# 0805_array.net
KiCad netlist of a schematic drawn in Altium Designer
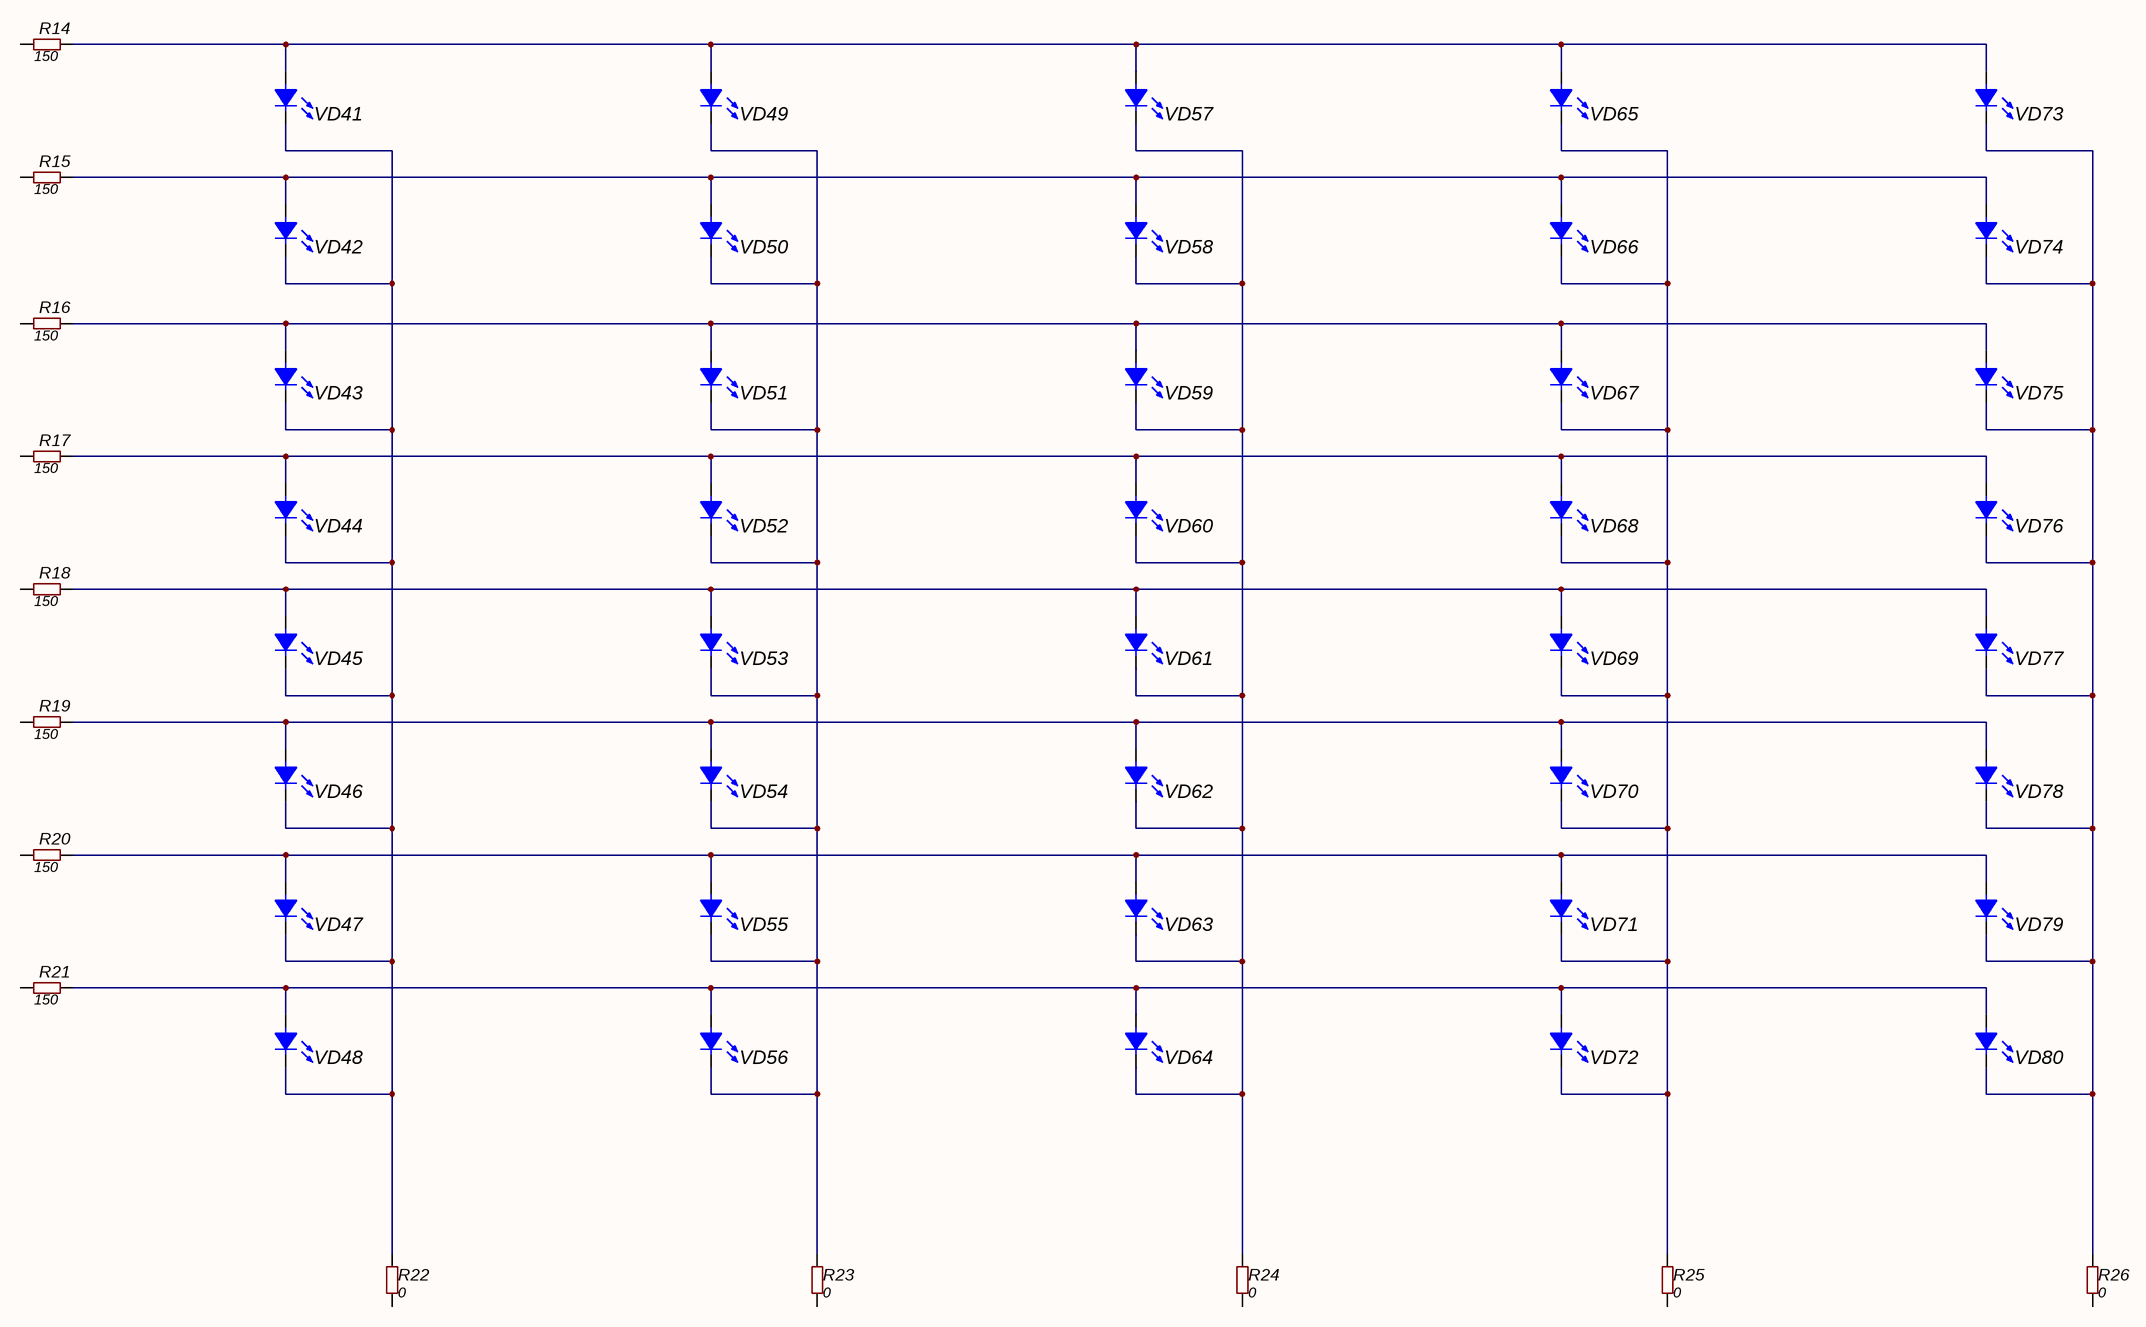
[diagram p0: 0805_array.SchDoc]

(export (version "E")
  (design (tool "Eeschema 10.0.6"))
  (components
    (comp (ref "R14")
      (value "150")
      (footprint "RES: 0603")
      (fields
        (field (name "MANUFACTURER") "Yageo")
        (field (name "PARTNUMBER") "RC0603JR-07100RL")
        (field (name "VALUEMANUFACTURERPARTNUMBER") "Resistor film, 150, , 0603, 0.1W, -55...+125°C")
      )
      (libsource (lib "") (part "Resistor_0603_1"))
    )
    (comp (ref "R15")
      (value "150")
      (footprint "RES: 0603")
      (fields
        (field (name "MANUFACTURER") "Yageo")
        (field (name "PARTNUMBER") "RC0603JR-07100RL")
        (field (name "VALUEMANUFACTURERPARTNUMBER") "Resistor film, 150, , 0603, 0.1W, -55...+125°C")
      )
      (libsource (lib "") (part "Resistor_0603_1"))
    )
    (comp (ref "R16")
      (value "150")
      (footprint "RES: 0603")
      (fields
        (field (name "MANUFACTURER") "Yageo")
        (field (name "PARTNUMBER") "RC0603JR-07100RL")
        (field (name "VALUEMANUFACTURERPARTNUMBER") "Resistor film, 150, , 0603, 0.1W, -55...+125°C")
      )
      (libsource (lib "") (part "Resistor_0603_1"))
    )
    (comp (ref "R17")
      (value "150")
      (footprint "RES: 0603")
      (fields
        (field (name "MANUFACTURER") "Yageo")
        (field (name "PARTNUMBER") "RC0603JR-07100RL")
        (field (name "VALUEMANUFACTURERPARTNUMBER") "Resistor film, 150, , 0603, 0.1W, -55...+125°C")
      )
      (libsource (lib "") (part "Resistor_0603_1"))
    )
    (comp (ref "R18")
      (value "150")
      (footprint "RES: 0603")
      (fields
        (field (name "MANUFACTURER") "Yageo")
        (field (name "PARTNUMBER") "RC0603JR-07100RL")
        (field (name "VALUEMANUFACTURERPARTNUMBER") "Resistor film, 150, , 0603, 0.1W, -55...+125°C")
      )
      (libsource (lib "") (part "Resistor_0603_1"))
    )
    (comp (ref "R19")
      (value "150")
      (footprint "RES: 0603")
      (fields
        (field (name "MANUFACTURER") "Yageo")
        (field (name "PARTNUMBER") "RC0603JR-07100RL")
        (field (name "VALUEMANUFACTURERPARTNUMBER") "Resistor film, 150, , 0603, 0.1W, -55...+125°C")
      )
      (libsource (lib "") (part "Resistor_0603_1"))
    )
    (comp (ref "R20")
      (value "150")
      (footprint "RES: 0603")
      (fields
        (field (name "MANUFACTURER") "Yageo")
        (field (name "PARTNUMBER") "RC0603JR-07100RL")
        (field (name "VALUEMANUFACTURERPARTNUMBER") "Resistor film, 150, , 0603, 0.1W, -55...+125°C")
      )
      (libsource (lib "") (part "Resistor_0603_1"))
    )
    (comp (ref "R21")
      (value "150")
      (footprint "RES: 0603")
      (fields
        (field (name "MANUFACTURER") "Yageo")
        (field (name "PARTNUMBER") "RC0603JR-07100RL")
        (field (name "VALUEMANUFACTURERPARTNUMBER") "Resistor film, 150, , 0603, 0.1W, -55...+125°C")
      )
      (libsource (lib "") (part "Resistor_0603_1"))
    )
    (comp (ref "R22")
      (value "0")
      (footprint "RES: 0603")
      (fields
        (field (name "MANUFACTURER") "Yageo")
        (field (name "PARTNUMBER") "RC0603JR-07100RL")
        (field (name "VALUEMANUFACTURERPARTNUMBER") "Resistor film, 0, , 0603, 0.1W, -55...+125°C")
      )
      (libsource (lib "resistor") (part "Resistor_0603"))
    )
    (comp (ref "R23")
      (value "0")
      (footprint "RES: 0603")
      (fields
        (field (name "MANUFACTURER") "Yageo")
        (field (name "PARTNUMBER") "RC0603JR-07100RL")
        (field (name "VALUEMANUFACTURERPARTNUMBER") "Resistor film, 0, , 0603, 0.1W, -55...+125°C")
      )
      (libsource (lib "resistor") (part "Resistor_0603"))
    )
    (comp (ref "R24")
      (value "0")
      (footprint "RES: 0603")
      (fields
        (field (name "MANUFACTURER") "Yageo")
        (field (name "PARTNUMBER") "RC0603JR-07100RL")
        (field (name "VALUEMANUFACTURERPARTNUMBER") "Resistor film, 0, , 0603, 0.1W, -55...+125°C")
      )
      (libsource (lib "resistor") (part "Resistor_0603"))
    )
    (comp (ref "R25")
      (value "0")
      (footprint "RES: 0603")
      (fields
        (field (name "MANUFACTURER") "Yageo")
        (field (name "PARTNUMBER") "RC0603JR-07100RL")
        (field (name "VALUEMANUFACTURERPARTNUMBER") "Resistor film, 0, , 0603, 0.1W, -55...+125°C")
      )
      (libsource (lib "resistor") (part "Resistor_0603"))
    )
    (comp (ref "R26")
      (value "0")
      (footprint "RES: 0603")
      (fields
        (field (name "MANUFACTURER") "Yageo")
        (field (name "PARTNUMBER") "RC0603JR-07100RL")
        (field (name "VALUEMANUFACTURERPARTNUMBER") "Resistor film, 0, , 0603, 0.1W, -55...+125°C")
      )
      (libsource (lib "resistor") (part "Resistor_0603"))
    )
    (comp (ref "VD41")
      (value "~")
      (footprint "LED: 0805Y")
      (fields (field (name "VALUEMANUFACTURERPARTNUMBER") "LED, Green, *, *, *, -55...+150°C"))
      (libsource (lib "diode") (part "LED_single"))
    )
    (comp (ref "VD42")
      (value "~")
      (footprint "LED: 0805Y")
      (fields (field (name "VALUEMANUFACTURERPARTNUMBER") "LED, Green, *, *, *, -55...+150°C"))
      (libsource (lib "diode") (part "LED_single"))
    )
    (comp (ref "VD43")
      (value "~")
      (footprint "LED: 0805Y")
      (fields (field (name "VALUEMANUFACTURERPARTNUMBER") "LED, Green, *, *, *, -55...+150°C"))
      (libsource (lib "diode") (part "LED_single"))
    )
    (comp (ref "VD44")
      (value "~")
      (footprint "LED: 0805Y")
      (fields (field (name "VALUEMANUFACTURERPARTNUMBER") "LED, Green, *, *, *, -55...+150°C"))
      (libsource (lib "diode") (part "LED_single"))
    )
    (comp (ref "VD45")
      (value "~")
      (footprint "LED: 0805Y")
      (fields (field (name "VALUEMANUFACTURERPARTNUMBER") "LED, Green, *, *, *, -55...+150°C"))
      (libsource (lib "diode") (part "LED_single"))
    )
    (comp (ref "VD46")
      (value "~")
      (footprint "LED: 0805Y")
      (fields (field (name "VALUEMANUFACTURERPARTNUMBER") "LED, Green, *, *, *, -55...+150°C"))
      (libsource (lib "diode") (part "LED_single"))
    )
    (comp (ref "VD47")
      (value "~")
      (footprint "LED: 0805Y")
      (fields (field (name "VALUEMANUFACTURERPARTNUMBER") "LED, Green, *, *, *, -55...+150°C"))
      (libsource (lib "diode") (part "LED_single"))
    )
    (comp (ref "VD48")
      (value "~")
      (footprint "LED: 0805Y")
      (fields (field (name "VALUEMANUFACTURERPARTNUMBER") "LED, Green, *, *, *, -55...+150°C"))
      (libsource (lib "diode") (part "LED_single"))
    )
    (comp (ref "VD49")
      (value "~")
      (footprint "LED: 0805Y")
      (fields (field (name "VALUEMANUFACTURERPARTNUMBER") "LED, Green, *, *, *, -55...+150°C"))
      (libsource (lib "diode") (part "LED_single"))
    )
    (comp (ref "VD50")
      (value "~")
      (footprint "LED: 0805Y")
      (fields (field (name "VALUEMANUFACTURERPARTNUMBER") "LED, Green, *, *, *, -55...+150°C"))
      (libsource (lib "diode") (part "LED_single"))
    )
    (comp (ref "VD51")
      (value "~")
      (footprint "LED: 0805Y")
      (fields (field (name "VALUEMANUFACTURERPARTNUMBER") "LED, Green, *, *, *, -55...+150°C"))
      (libsource (lib "diode") (part "LED_single"))
    )
    (comp (ref "VD52")
      (value "~")
      (footprint "LED: 0805Y")
      (fields (field (name "VALUEMANUFACTURERPARTNUMBER") "LED, Green, *, *, *, -55...+150°C"))
      (libsource (lib "diode") (part "LED_single"))
    )
    (comp (ref "VD53")
      (value "~")
      (footprint "LED: 0805Y")
      (fields (field (name "VALUEMANUFACTURERPARTNUMBER") "LED, Green, *, *, *, -55...+150°C"))
      (libsource (lib "diode") (part "LED_single"))
    )
    (comp (ref "VD54")
      (value "~")
      (footprint "LED: 0805Y")
      (fields (field (name "VALUEMANUFACTURERPARTNUMBER") "LED, Green, *, *, *, -55...+150°C"))
      (libsource (lib "diode") (part "LED_single"))
    )
    (comp (ref "VD55")
      (value "~")
      (footprint "LED: 0805Y")
      (fields (field (name "VALUEMANUFACTURERPARTNUMBER") "LED, Green, *, *, *, -55...+150°C"))
      (libsource (lib "diode") (part "LED_single"))
    )
    (comp (ref "VD56")
      (value "~")
      (footprint "LED: 0805Y")
      (fields (field (name "VALUEMANUFACTURERPARTNUMBER") "LED, Green, *, *, *, -55...+150°C"))
      (libsource (lib "diode") (part "LED_single"))
    )
    (comp (ref "VD57")
      (value "~")
      (footprint "LED: 0805Y")
      (fields (field (name "VALUEMANUFACTURERPARTNUMBER") "LED, Green, *, *, *, -55...+150°C"))
      (libsource (lib "diode") (part "LED_single"))
    )
    (comp (ref "VD58")
      (value "~")
      (footprint "LED: 0805Y")
      (fields (field (name "VALUEMANUFACTURERPARTNUMBER") "LED, Green, *, *, *, -55...+150°C"))
      (libsource (lib "diode") (part "LED_single"))
    )
    (comp (ref "VD59")
      (value "~")
      (footprint "LED: 0805Y")
      (fields (field (name "VALUEMANUFACTURERPARTNUMBER") "LED, Green, *, *, *, -55...+150°C"))
      (libsource (lib "diode") (part "LED_single"))
    )
    (comp (ref "VD60")
      (value "~")
      (footprint "LED: 0805Y")
      (fields (field (name "VALUEMANUFACTURERPARTNUMBER") "LED, Green, *, *, *, -55...+150°C"))
      (libsource (lib "diode") (part "LED_single"))
    )
    (comp (ref "VD61")
      (value "~")
      (footprint "LED: 0805Y")
      (fields (field (name "VALUEMANUFACTURERPARTNUMBER") "LED, Green, *, *, *, -55...+150°C"))
      (libsource (lib "diode") (part "LED_single"))
    )
    (comp (ref "VD62")
      (value "~")
      (footprint "LED: 0805Y")
      (fields (field (name "VALUEMANUFACTURERPARTNUMBER") "LED, Green, *, *, *, -55...+150°C"))
      (libsource (lib "diode") (part "LED_single"))
    )
    (comp (ref "VD63")
      (value "~")
      (footprint "LED: 0805Y")
      (fields (field (name "VALUEMANUFACTURERPARTNUMBER") "LED, Green, *, *, *, -55...+150°C"))
      (libsource (lib "diode") (part "LED_single"))
    )
    (comp (ref "VD64")
      (value "~")
      (footprint "LED: 0805Y")
      (fields (field (name "VALUEMANUFACTURERPARTNUMBER") "LED, Green, *, *, *, -55...+150°C"))
      (libsource (lib "diode") (part "LED_single"))
    )
    (comp (ref "VD65")
      (value "~")
      (footprint "LED: 0805Y")
      (fields (field (name "VALUEMANUFACTURERPARTNUMBER") "LED, Green, *, *, *, -55...+150°C"))
      (libsource (lib "diode") (part "LED_single"))
    )
    (comp (ref "VD66")
      (value "~")
      (footprint "LED: 0805Y")
      (fields (field (name "VALUEMANUFACTURERPARTNUMBER") "LED, Green, *, *, *, -55...+150°C"))
      (libsource (lib "diode") (part "LED_single"))
    )
    (comp (ref "VD67")
      (value "~")
      (footprint "LED: 0805Y")
      (fields (field (name "VALUEMANUFACTURERPARTNUMBER") "LED, Green, *, *, *, -55...+150°C"))
      (libsource (lib "diode") (part "LED_single"))
    )
    (comp (ref "VD68")
      (value "~")
      (footprint "LED: 0805Y")
      (fields (field (name "VALUEMANUFACTURERPARTNUMBER") "LED, Green, *, *, *, -55...+150°C"))
      (libsource (lib "diode") (part "LED_single"))
    )
    (comp (ref "VD69")
      (value "~")
      (footprint "LED: 0805Y")
      (fields (field (name "VALUEMANUFACTURERPARTNUMBER") "LED, Green, *, *, *, -55...+150°C"))
      (libsource (lib "diode") (part "LED_single"))
    )
    (comp (ref "VD70")
      (value "~")
      (footprint "LED: 0805Y")
      (fields (field (name "VALUEMANUFACTURERPARTNUMBER") "LED, Green, *, *, *, -55...+150°C"))
      (libsource (lib "diode") (part "LED_single"))
    )
    (comp (ref "VD71")
      (value "~")
      (footprint "LED: 0805Y")
      (fields (field (name "VALUEMANUFACTURERPARTNUMBER") "LED, Green, *, *, *, -55...+150°C"))
      (libsource (lib "diode") (part "LED_single"))
    )
    (comp (ref "VD72")
      (value "~")
      (footprint "LED: 0805Y")
      (fields (field (name "VALUEMANUFACTURERPARTNUMBER") "LED, Green, *, *, *, -55...+150°C"))
      (libsource (lib "diode") (part "LED_single"))
    )
    (comp (ref "VD73")
      (value "~")
      (footprint "LED: 0805Y")
      (fields (field (name "VALUEMANUFACTURERPARTNUMBER") "LED, Green, *, *, *, -55...+150°C"))
      (libsource (lib "diode") (part "LED_single"))
    )
    (comp (ref "VD74")
      (value "~")
      (footprint "LED: 0805Y")
      (fields (field (name "VALUEMANUFACTURERPARTNUMBER") "LED, Green, *, *, *, -55...+150°C"))
      (libsource (lib "diode") (part "LED_single"))
    )
    (comp (ref "VD75")
      (value "~")
      (footprint "LED: 0805Y")
      (fields (field (name "VALUEMANUFACTURERPARTNUMBER") "LED, Green, *, *, *, -55...+150°C"))
      (libsource (lib "diode") (part "LED_single"))
    )
    (comp (ref "VD76")
      (value "~")
      (footprint "LED: 0805Y")
      (fields (field (name "VALUEMANUFACTURERPARTNUMBER") "LED, Green, *, *, *, -55...+150°C"))
      (libsource (lib "diode") (part "LED_single"))
    )
    (comp (ref "VD77")
      (value "~")
      (footprint "LED: 0805Y")
      (fields (field (name "VALUEMANUFACTURERPARTNUMBER") "LED, Green, *, *, *, -55...+150°C"))
      (libsource (lib "diode") (part "LED_single"))
    )
    (comp (ref "VD78")
      (value "~")
      (footprint "LED: 0805Y")
      (fields (field (name "VALUEMANUFACTURERPARTNUMBER") "LED, Green, *, *, *, -55...+150°C"))
      (libsource (lib "diode") (part "LED_single"))
    )
    (comp (ref "VD79")
      (value "~")
      (footprint "LED: 0805Y")
      (fields (field (name "VALUEMANUFACTURERPARTNUMBER") "LED, Green, *, *, *, -55...+150°C"))
      (libsource (lib "diode") (part "LED_single"))
    )
    (comp (ref "VD80")
      (value "~")
      (footprint "LED: 0805Y")
      (fields (field (name "VALUEMANUFACTURERPARTNUMBER") "LED, Green, *, *, *, -55...+150°C"))
      (libsource (lib "diode") (part "LED_single"))
    )
  )
  (nets
    (net (code "1") (name "Net-(VD41-A)") (class "Default")
      (node (ref "R14") (pin "2") (pinfunction "2_2") (pintype "passive"))
      (node (ref "VD41") (pin "1") (pinfunction "A_1") (pintype "passive"))
      (node (ref "VD49") (pin "1") (pinfunction "A_1") (pintype "passive"))
      (node (ref "VD57") (pin "1") (pinfunction "A_1") (pintype "passive"))
      (node (ref "VD65") (pin "1") (pinfunction "A_1") (pintype "passive"))
      (node (ref "VD73") (pin "1") (pinfunction "A_1") (pintype "passive"))
    )
    (net (code "2") (name "Net-(VD41-C)") (class "Default")
      (node (ref "R22") (pin "2") (pinfunction "2_2") (pintype "passive"))
      (node (ref "VD41") (pin "2") (pinfunction "C_2") (pintype "passive"))
      (node (ref "VD42") (pin "2") (pinfunction "C_2") (pintype "passive"))
      (node (ref "VD43") (pin "2") (pinfunction "C_2") (pintype "passive"))
      (node (ref "VD44") (pin "2") (pinfunction "C_2") (pintype "passive"))
      (node (ref "VD45") (pin "2") (pinfunction "C_2") (pintype "passive"))
      (node (ref "VD46") (pin "2") (pinfunction "C_2") (pintype "passive"))
      (node (ref "VD47") (pin "2") (pinfunction "C_2") (pintype "passive"))
      (node (ref "VD48") (pin "2") (pinfunction "C_2") (pintype "passive"))
    )
    (net (code "3") (name "Net-(VD42-A)") (class "Default")
      (node (ref "R15") (pin "2") (pinfunction "2_2") (pintype "passive"))
      (node (ref "VD42") (pin "1") (pinfunction "A_1") (pintype "passive"))
      (node (ref "VD50") (pin "1") (pinfunction "A_1") (pintype "passive"))
      (node (ref "VD58") (pin "1") (pinfunction "A_1") (pintype "passive"))
      (node (ref "VD66") (pin "1") (pinfunction "A_1") (pintype "passive"))
      (node (ref "VD74") (pin "1") (pinfunction "A_1") (pintype "passive"))
    )
    (net (code "4") (name "Net-(VD43-A)") (class "Default")
      (node (ref "R16") (pin "2") (pinfunction "2_2") (pintype "passive"))
      (node (ref "VD43") (pin "1") (pinfunction "A_1") (pintype "passive"))
      (node (ref "VD51") (pin "1") (pinfunction "A_1") (pintype "passive"))
      (node (ref "VD59") (pin "1") (pinfunction "A_1") (pintype "passive"))
      (node (ref "VD67") (pin "1") (pinfunction "A_1") (pintype "passive"))
      (node (ref "VD75") (pin "1") (pinfunction "A_1") (pintype "passive"))
    )
    (net (code "5") (name "Net-(VD44-A)") (class "Default")
      (node (ref "R17") (pin "2") (pinfunction "2_2") (pintype "passive"))
      (node (ref "VD44") (pin "1") (pinfunction "A_1") (pintype "passive"))
      (node (ref "VD52") (pin "1") (pinfunction "A_1") (pintype "passive"))
      (node (ref "VD60") (pin "1") (pinfunction "A_1") (pintype "passive"))
      (node (ref "VD68") (pin "1") (pinfunction "A_1") (pintype "passive"))
      (node (ref "VD76") (pin "1") (pinfunction "A_1") (pintype "passive"))
    )
    (net (code "6") (name "Net-(VD45-A)") (class "Default")
      (node (ref "R18") (pin "2") (pinfunction "2_2") (pintype "passive"))
      (node (ref "VD45") (pin "1") (pinfunction "A_1") (pintype "passive"))
      (node (ref "VD53") (pin "1") (pinfunction "A_1") (pintype "passive"))
      (node (ref "VD61") (pin "1") (pinfunction "A_1") (pintype "passive"))
      (node (ref "VD69") (pin "1") (pinfunction "A_1") (pintype "passive"))
      (node (ref "VD77") (pin "1") (pinfunction "A_1") (pintype "passive"))
    )
    (net (code "7") (name "Net-(VD46-A)") (class "Default")
      (node (ref "R19") (pin "2") (pinfunction "2_2") (pintype "passive"))
      (node (ref "VD46") (pin "1") (pinfunction "A_1") (pintype "passive"))
      (node (ref "VD54") (pin "1") (pinfunction "A_1") (pintype "passive"))
      (node (ref "VD62") (pin "1") (pinfunction "A_1") (pintype "passive"))
      (node (ref "VD70") (pin "1") (pinfunction "A_1") (pintype "passive"))
      (node (ref "VD78") (pin "1") (pinfunction "A_1") (pintype "passive"))
    )
    (net (code "8") (name "Net-(VD47-A)") (class "Default")
      (node (ref "R20") (pin "2") (pinfunction "2_2") (pintype "passive"))
      (node (ref "VD47") (pin "1") (pinfunction "A_1") (pintype "passive"))
      (node (ref "VD55") (pin "1") (pinfunction "A_1") (pintype "passive"))
      (node (ref "VD63") (pin "1") (pinfunction "A_1") (pintype "passive"))
      (node (ref "VD71") (pin "1") (pinfunction "A_1") (pintype "passive"))
      (node (ref "VD79") (pin "1") (pinfunction "A_1") (pintype "passive"))
    )
    (net (code "9") (name "Net-(VD48-A)") (class "Default")
      (node (ref "R21") (pin "2") (pinfunction "2_2") (pintype "passive"))
      (node (ref "VD48") (pin "1") (pinfunction "A_1") (pintype "passive"))
      (node (ref "VD56") (pin "1") (pinfunction "A_1") (pintype "passive"))
      (node (ref "VD64") (pin "1") (pinfunction "A_1") (pintype "passive"))
      (node (ref "VD72") (pin "1") (pinfunction "A_1") (pintype "passive"))
      (node (ref "VD80") (pin "1") (pinfunction "A_1") (pintype "passive"))
    )
    (net (code "10") (name "Net-(VD49-C)") (class "Default")
      (node (ref "R23") (pin "2") (pinfunction "2_2") (pintype "passive"))
      (node (ref "VD49") (pin "2") (pinfunction "C_2") (pintype "passive"))
      (node (ref "VD50") (pin "2") (pinfunction "C_2") (pintype "passive"))
      (node (ref "VD51") (pin "2") (pinfunction "C_2") (pintype "passive"))
      (node (ref "VD52") (pin "2") (pinfunction "C_2") (pintype "passive"))
      (node (ref "VD53") (pin "2") (pinfunction "C_2") (pintype "passive"))
      (node (ref "VD54") (pin "2") (pinfunction "C_2") (pintype "passive"))
      (node (ref "VD55") (pin "2") (pinfunction "C_2") (pintype "passive"))
      (node (ref "VD56") (pin "2") (pinfunction "C_2") (pintype "passive"))
    )
    (net (code "11") (name "Net-(VD57-C)") (class "Default")
      (node (ref "R24") (pin "2") (pinfunction "2_2") (pintype "passive"))
      (node (ref "VD57") (pin "2") (pinfunction "C_2") (pintype "passive"))
      (node (ref "VD58") (pin "2") (pinfunction "C_2") (pintype "passive"))
      (node (ref "VD59") (pin "2") (pinfunction "C_2") (pintype "passive"))
      (node (ref "VD60") (pin "2") (pinfunction "C_2") (pintype "passive"))
      (node (ref "VD61") (pin "2") (pinfunction "C_2") (pintype "passive"))
      (node (ref "VD62") (pin "2") (pinfunction "C_2") (pintype "passive"))
      (node (ref "VD63") (pin "2") (pinfunction "C_2") (pintype "passive"))
      (node (ref "VD64") (pin "2") (pinfunction "C_2") (pintype "passive"))
    )
    (net (code "12") (name "Net-(VD65-C)") (class "Default")
      (node (ref "R25") (pin "2") (pinfunction "2_2") (pintype "passive"))
      (node (ref "VD65") (pin "2") (pinfunction "C_2") (pintype "passive"))
      (node (ref "VD66") (pin "2") (pinfunction "C_2") (pintype "passive"))
      (node (ref "VD67") (pin "2") (pinfunction "C_2") (pintype "passive"))
      (node (ref "VD68") (pin "2") (pinfunction "C_2") (pintype "passive"))
      (node (ref "VD69") (pin "2") (pinfunction "C_2") (pintype "passive"))
      (node (ref "VD70") (pin "2") (pinfunction "C_2") (pintype "passive"))
      (node (ref "VD71") (pin "2") (pinfunction "C_2") (pintype "passive"))
      (node (ref "VD72") (pin "2") (pinfunction "C_2") (pintype "passive"))
    )
    (net (code "13") (name "Net-(VD73-C)") (class "Default")
      (node (ref "R26") (pin "2") (pinfunction "2_2") (pintype "passive"))
      (node (ref "VD73") (pin "2") (pinfunction "C_2") (pintype "passive"))
      (node (ref "VD74") (pin "2") (pinfunction "C_2") (pintype "passive"))
      (node (ref "VD75") (pin "2") (pinfunction "C_2") (pintype "passive"))
      (node (ref "VD76") (pin "2") (pinfunction "C_2") (pintype "passive"))
      (node (ref "VD77") (pin "2") (pinfunction "C_2") (pintype "passive"))
      (node (ref "VD78") (pin "2") (pinfunction "C_2") (pintype "passive"))
      (node (ref "VD79") (pin "2") (pinfunction "C_2") (pintype "passive"))
      (node (ref "VD80") (pin "2") (pinfunction "C_2") (pintype "passive"))
    )
    (net (code "14") (name "unconnected-(R14-Pad1)") (class "Default")
      (node (ref "R14") (pin "1") (pinfunction "1_1") (pintype "passive"))
    )
    (net (code "15") (name "unconnected-(R15-Pad1)") (class "Default")
      (node (ref "R15") (pin "1") (pinfunction "1_1") (pintype "passive"))
    )
    (net (code "16") (name "unconnected-(R16-Pad1)") (class "Default")
      (node (ref "R16") (pin "1") (pinfunction "1_1") (pintype "passive"))
    )
    (net (code "17") (name "unconnected-(R17-Pad1)") (class "Default")
      (node (ref "R17") (pin "1") (pinfunction "1_1") (pintype "passive"))
    )
    (net (code "18") (name "unconnected-(R18-Pad1)") (class "Default")
      (node (ref "R18") (pin "1") (pinfunction "1_1") (pintype "passive"))
    )
    (net (code "19") (name "unconnected-(R19-Pad1)") (class "Default")
      (node (ref "R19") (pin "1") (pinfunction "1_1") (pintype "passive"))
    )
    (net (code "20") (name "unconnected-(R20-Pad1)") (class "Default")
      (node (ref "R20") (pin "1") (pinfunction "1_1") (pintype "passive"))
    )
    (net (code "21") (name "unconnected-(R21-Pad1)") (class "Default")
      (node (ref "R21") (pin "1") (pinfunction "1_1") (pintype "passive"))
    )
    (net (code "22") (name "unconnected-(R22-Pad1)") (class "Default")
      (node (ref "R22") (pin "1") (pinfunction "1_1") (pintype "passive"))
    )
    (net (code "23") (name "unconnected-(R23-Pad1)") (class "Default")
      (node (ref "R23") (pin "1") (pinfunction "1_1") (pintype "passive"))
    )
    (net (code "24") (name "unconnected-(R24-Pad1)") (class "Default")
      (node (ref "R24") (pin "1") (pinfunction "1_1") (pintype "passive"))
    )
    (net (code "25") (name "unconnected-(R25-Pad1)") (class "Default")
      (node (ref "R25") (pin "1") (pinfunction "1_1") (pintype "passive"))
    )
    (net (code "26") (name "unconnected-(R26-Pad1)") (class "Default")
      (node (ref "R26") (pin "1") (pinfunction "1_1") (pintype "passive"))
    )
  )
)
